# maintenance_panel.net
KiCad netlist of a schematic drawn in EAGLE
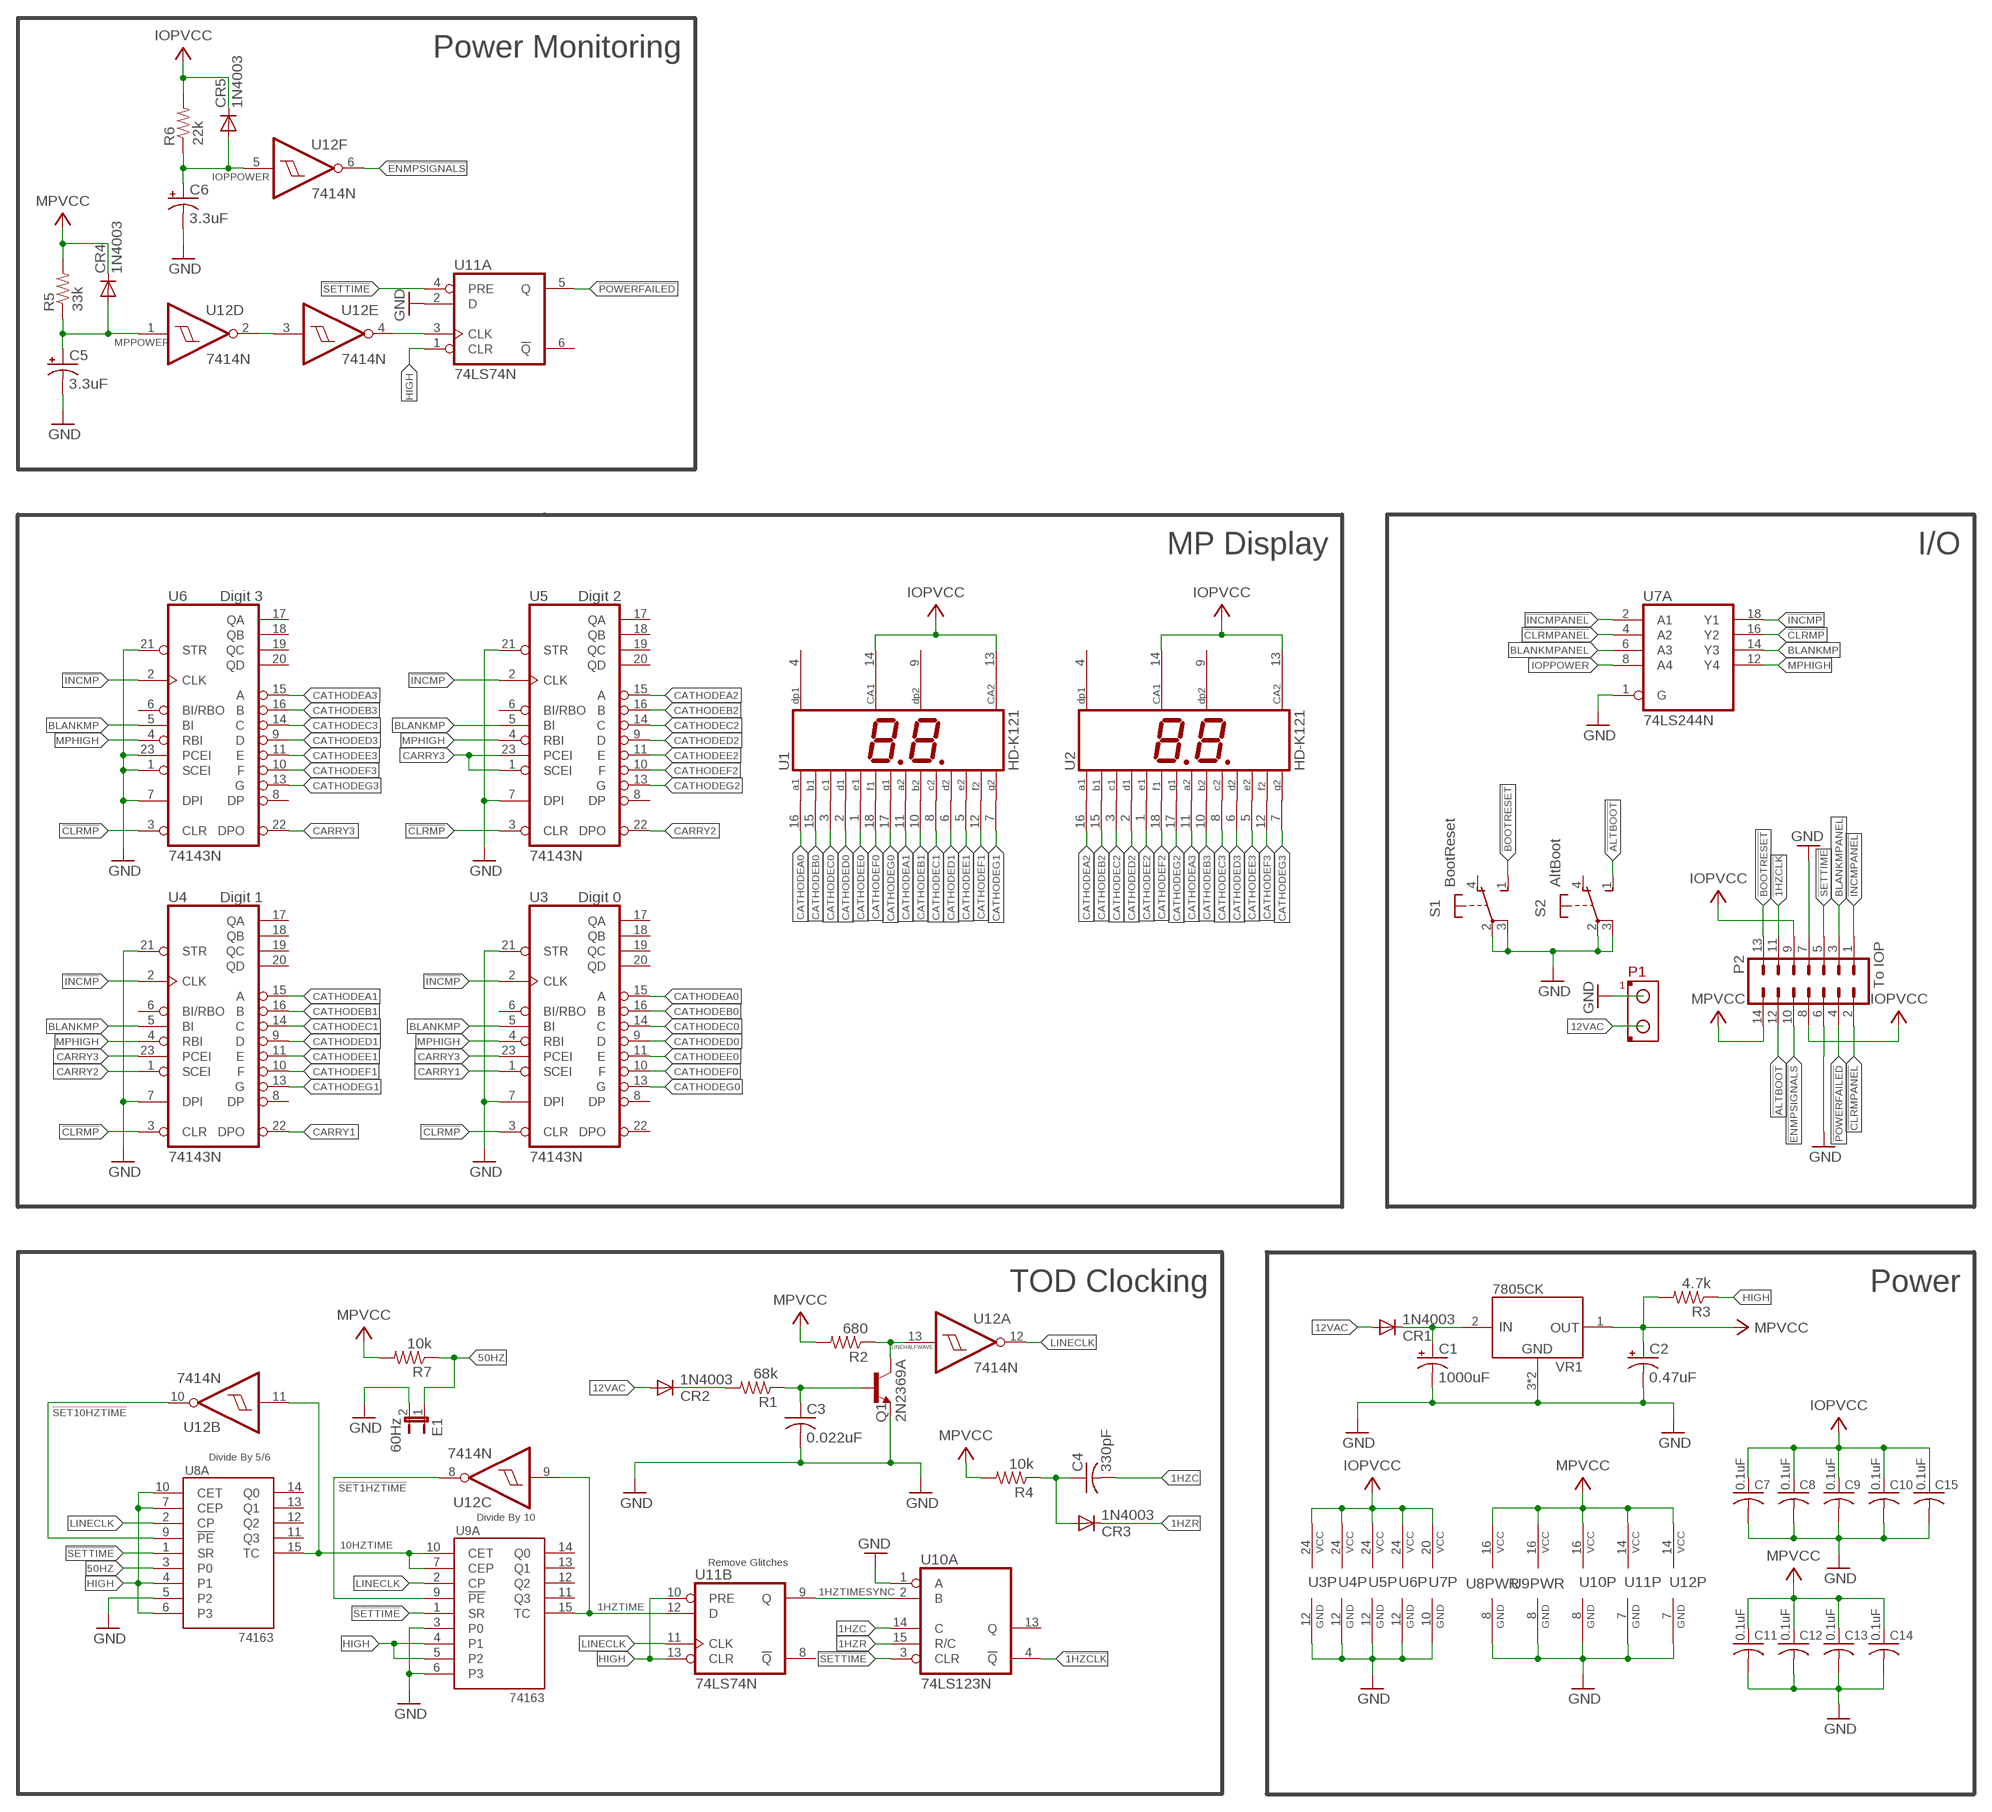
[diagram p0: schematic, sheet 1]

(export (version "E")
  (design (tool "Eeschema 10.0.6"))
  (components
    (comp (ref "C1")
      (value "1000uF")
      (footprint "eagle-import:E25-10")
      (libsource (lib "eagle-import") (part "CPOL-USE25-10AXIAL"))
    )
    (comp (ref "C2")
      (value "0.47uF")
      (footprint "eagle-import:E15-5")
      (libsource (lib "eagle-import") (part "CPOL-USE15-5AXIAL"))
    )
    (comp (ref "C3")
      (value "0.022uF")
      (footprint "eagle-import:C075-052X106")
      (libsource (lib "eagle-import") (part "C-US075-052X106"))
    )
    (comp (ref "C4")
      (value "330pF")
      (footprint "eagle-import:C075-032X103")
      (libsource (lib "eagle-import") (part "C-US075-032X103"))
    )
    (comp (ref "C5")
      (value "3.3uF")
      (footprint "eagle-import:E15-5")
      (libsource (lib "eagle-import") (part "CPOL-USE15-5AXIAL"))
    )
    (comp (ref "C6")
      (value "3.3uF")
      (footprint "eagle-import:E15-5")
      (libsource (lib "eagle-import") (part "CPOL-USE15-5AXIAL"))
    )
    (comp (ref "C7")
      (value "0.1uF")
      (footprint "eagle-import:C075-032X103")
      (libsource (lib "eagle-import") (part "C-US075-032X103"))
    )
    (comp (ref "C8")
      (value "0.1uF")
      (footprint "eagle-import:C075-032X103")
      (libsource (lib "eagle-import") (part "C-US075-032X103"))
    )
    (comp (ref "C9")
      (value "0.1uF")
      (footprint "eagle-import:C075-032X103")
      (libsource (lib "eagle-import") (part "C-US075-032X103"))
    )
    (comp (ref "C10")
      (value "0.1uF")
      (footprint "eagle-import:C075-032X103")
      (libsource (lib "eagle-import") (part "C-US075-032X103"))
    )
    (comp (ref "C11")
      (value "0.1uF")
      (footprint "eagle-import:C075-032X103")
      (libsource (lib "eagle-import") (part "C-US075-032X103"))
    )
    (comp (ref "C12")
      (value "0.1uF")
      (footprint "eagle-import:C075-032X103")
      (libsource (lib "eagle-import") (part "C-US075-032X103"))
    )
    (comp (ref "C13")
      (value "0.1uF")
      (footprint "eagle-import:C075-032X103")
      (libsource (lib "eagle-import") (part "C-US075-032X103"))
    )
    (comp (ref "C14")
      (value "0.1uF")
      (footprint "eagle-import:C075-032X103")
      (libsource (lib "eagle-import") (part "C-US075-032X103"))
    )
    (comp (ref "C15")
      (value "0.1uF")
      (footprint "eagle-import:C075-032X103")
      (libsource (lib "eagle-import") (part "C-US075-032X103"))
    )
    (comp (ref "CR1")
      (value "1N4003")
      (footprint "eagle-import:DO41-10")
      (libsource (lib "eagle-import") (part "1N4004"))
    )
    (comp (ref "CR2")
      (value "1N4003")
      (footprint "eagle-import:DO41-10")
      (libsource (lib "eagle-import") (part "1N4004"))
    )
    (comp (ref "CR3")
      (value "1N4003")
      (footprint "eagle-import:DO41-10")
      (libsource (lib "eagle-import") (part "1N4004"))
    )
    (comp (ref "CR4")
      (value "1N4003")
      (footprint "eagle-import:DO41-10")
      (libsource (lib "eagle-import") (part "1N4004"))
    )
    (comp (ref "CR5")
      (value "1N4003")
      (footprint "eagle-import:DO41-10")
      (libsource (lib "eagle-import") (part "1N4004"))
    )
    (comp (ref "E1")
      (value "60Hz")
      (footprint "eagle-import:JP1")
      (libsource (lib "eagle-import") (part "JP1E"))
    )
    (comp (ref "P1")
      (value "XEROX-RTC-2X1")
      (footprint "eagle-import:XEROX-RTC-2X1")
      (libsource (lib "eagle-import") (part "XEROX-RTC-2X1"))
    )
    (comp (ref "P2")
      (value "To IOP")
      (footprint "eagle-import:MA07-2")
      (libsource (lib "eagle-import") (part "MA07-2"))
    )
    (comp (ref "Q1")
      (value "2N2369A")
      (footprint "eagle-import:TO18")
      (libsource (lib "eagle-import") (part "-NPN-TO18-EBC2N2369A"))
    )
    (comp (ref "R1")
      (value "68k")
      (footprint "eagle-import:0207_10")
      (libsource (lib "eagle-import") (part "R-US_0207/10"))
    )
    (comp (ref "R2")
      (value "680")
      (footprint "eagle-import:0207_10")
      (libsource (lib "eagle-import") (part "R-US_0207/10"))
    )
    (comp (ref "R3")
      (value "4.7k")
      (footprint "eagle-import:0207_10")
      (libsource (lib "eagle-import") (part "R-US_0207/10"))
    )
    (comp (ref "R4")
      (value "10k")
      (footprint "eagle-import:0207_10")
      (libsource (lib "eagle-import") (part "R-US_0207/10"))
    )
    (comp (ref "R5")
      (value "33k")
      (footprint "eagle-import:0207_10")
      (libsource (lib "eagle-import") (part "R-US_0207/10"))
    )
    (comp (ref "R6")
      (value "22k")
      (footprint "eagle-import:0207_10")
      (libsource (lib "eagle-import") (part "R-US_0207/10"))
    )
    (comp (ref "R7")
      (value "10k")
      (footprint "eagle-import:0207_10")
      (libsource (lib "eagle-import") (part "R-US_0207/10"))
    )
    (comp (ref "S1")
      (value "BootReset")
      (footprint "eagle-import:SRK")
      (libsource (lib "eagle-import") (part "SRK"))
    )
    (comp (ref "S2")
      (value "AltBoot")
      (footprint "eagle-import:SRK")
      (libsource (lib "eagle-import") (part "SRK"))
    )
    (comp (ref "U1")
      (value "HD-K121")
      (footprint "eagle-import:HDSP-R")
      (libsource (lib "eagle-import") (part "HD-K121"))
    )
    (comp (ref "U2")
      (value "HD-K121")
      (footprint "eagle-import:HDSP-R")
      (libsource (lib "eagle-import") (part "HD-K121"))
    )
    (comp (ref "U3")
      (value "74143N")
      (footprint "eagle-import:DIL24-6")
      (libsource (lib "eagle-import") (part "74143N"))
    )
    (comp (ref "U4")
      (value "74143N")
      (footprint "eagle-import:DIL24-6")
      (libsource (lib "eagle-import") (part "74143N"))
    )
    (comp (ref "U5")
      (value "74143N")
      (footprint "eagle-import:DIL24-6")
      (libsource (lib "eagle-import") (part "74143N"))
    )
    (comp (ref "U6")
      (value "74143N")
      (footprint "eagle-import:DIL24-6")
      (libsource (lib "eagle-import") (part "74143N"))
    )
    (comp (ref "U7")
      (value "74LS244N")
      (footprint "eagle-import:DIL20")
      (libsource (lib "eagle-import") (part "74244NLS"))
    )
    (comp (ref "U8")
      (value "74163")
      (footprint "eagle-import:DIL16")
      (libsource (lib "eagle-import") (part "74163"))
    )
    (comp (ref "U9")
      (value "74163")
      (footprint "eagle-import:DIL16")
      (libsource (lib "eagle-import") (part "74163"))
    )
    (comp (ref "U10")
      (value "74LS123N")
      (footprint "eagle-import:DIL16")
      (libsource (lib "eagle-import") (part "74123NLS"))
    )
    (comp (ref "U11")
      (value "74LS74N")
      (footprint "eagle-import:DIL14")
      (libsource (lib "eagle-import") (part "7474NLS"))
    )
    (comp (ref "U12")
      (value "7414N")
      (footprint "eagle-import:DIL14")
      (libsource (lib "eagle-import") (part "7414N"))
    )
    (comp (ref "VR1")
      (value "7805CK")
      (footprint "eagle-import:TO3-78")
      (libsource (lib "eagle-import") (part "7805CK"))
    )
  )
  (nets
    (net (code "1") (name "/1HZTIME") (class "Default")
      (node (ref "U11") (pin "12") (pinfunction "D_12") (pintype "input"))
      (node (ref "U12") (pin "9") (pinfunction "I_9") (pintype "input"))
      (node (ref "U9") (pin "15") (pinfunction "TC_15") (pintype "output"))
    )
    (net (code "2") (name "/1HZTIMESYNC") (class "Default")
      (node (ref "U10") (pin "2") (pinfunction "B_2") (pintype "input"))
      (node (ref "U11") (pin "9") (pinfunction "Q_9") (pintype "output"))
    )
    (net (code "3") (name "/10HZTIME") (class "Default")
      (node (ref "U12") (pin "11") (pinfunction "I_11") (pintype "input"))
      (node (ref "U8") (pin "15") (pinfunction "TC_15") (pintype "output"))
      (node (ref "U9") (pin "10") (pinfunction "CET_10") (pintype "input"))
      (node (ref "U9") (pin "7") (pinfunction "CEP_7") (pintype "input"))
    )
    (net (code "4") (name "/LINEHALFWAVE") (class "Default")
      (node (ref "Q1") (pin "3") (pinfunction "C_3") (pintype "passive"))
      (node (ref "R2") (pin "1") (pinfunction "1_1") (pintype "passive"))
      (node (ref "U12") (pin "13") (pinfunction "I_13") (pintype "input"))
    )
    (net (code "5") (name "/MPPOWER") (class "Default")
      (node (ref "C5") (pin "+") (pinfunction "+_+") (pintype "passive"))
      (node (ref "CR4") (pin "A") (pinfunction "A_A") (pintype "passive"))
      (node (ref "R5") (pin "1") (pinfunction "1_1") (pintype "passive"))
      (node (ref "U12") (pin "1") (pinfunction "I_1") (pintype "input"))
    )
    (net (code "6") (name "/~{1HZCLK}") (class "Default")
      (node (ref "P2") (pin "11") (pinfunction "11_11") (pintype "passive"))
      (node (ref "U10") (pin "4") (pinfunction "~{Q}_4") (pintype "output"))
    )
    (net (code "7") (name "/~{ALTBOOT}") (class "Default")
      (node (ref "P2") (pin "12") (pinfunction "12_12") (pintype "passive"))
      (node (ref "S2") (pin "1") (pinfunction "S_1") (pintype "passive"))
    )
    (net (code "8") (name "/~{BOOTRESET}") (class "Default")
      (node (ref "P2") (pin "13") (pinfunction "13_13") (pintype "passive"))
      (node (ref "S1") (pin "1") (pinfunction "S_1") (pintype "passive"))
    )
    (net (code "9") (name "/~{CLRMPANEL}") (class "Default")
      (node (ref "P2") (pin "2") (pinfunction "2_2") (pintype "passive"))
      (node (ref "U7") (pin "4") (pinfunction "A2_4") (pintype "input"))
    )
    (net (code "10") (name "/~{CLRMP}") (class "Default")
      (node (ref "U3") (pin "3") (pinfunction "CLR_3") (pintype "input"))
      (node (ref "U4") (pin "3") (pinfunction "CLR_3") (pintype "input"))
      (node (ref "U5") (pin "3") (pinfunction "CLR_3") (pintype "input"))
      (node (ref "U6") (pin "3") (pinfunction "CLR_3") (pintype "input"))
      (node (ref "U7") (pin "16") (pinfunction "Y2_16") (pintype "tri_state"))
    )
    (net (code "11") (name "/~{ENMPSIGNALS}") (class "Default")
      (node (ref "P2") (pin "10") (pinfunction "10_10") (pintype "passive"))
      (node (ref "U12") (pin "6") (pinfunction "O_6") (pintype "output"))
    )
    (net (code "12") (name "/~{INCMPANEL}") (class "Default")
      (node (ref "P2") (pin "1") (pinfunction "1_1") (pintype "passive"))
      (node (ref "U7") (pin "2") (pinfunction "A1_2") (pintype "input"))
    )
    (net (code "13") (name "/~{INCMP}") (class "Default")
      (node (ref "U3") (pin "2") (pinfunction "CLK_2") (pintype "input"))
      (node (ref "U4") (pin "2") (pinfunction "CLK_2") (pintype "input"))
      (node (ref "U5") (pin "2") (pinfunction "CLK_2") (pintype "input"))
      (node (ref "U6") (pin "2") (pinfunction "CLK_2") (pintype "input"))
      (node (ref "U7") (pin "18") (pinfunction "Y1_18") (pintype "tri_state"))
    )
    (net (code "14") (name "/~{POWERFAILED}") (class "Default")
      (node (ref "P2") (pin "4") (pinfunction "4_4") (pintype "passive"))
      (node (ref "U11") (pin "5") (pinfunction "Q_5") (pintype "output"))
    )
    (net (code "15") (name "/~{SET1HZTIME}") (class "Default")
      (node (ref "U12") (pin "8") (pinfunction "O_8") (pintype "output"))
      (node (ref "U9") (pin "9") (pinfunction "~{PE}_9") (pintype "input"))
    )
    (net (code "16") (name "/~{SET10HZTIME}") (class "Default")
      (node (ref "U12") (pin "10") (pinfunction "O_10") (pintype "output"))
      (node (ref "U8") (pin "9") (pinfunction "~{PE}_9") (pintype "input"))
    )
    (net (code "17") (name "/~{SETTIME}") (class "Default")
      (node (ref "P2") (pin "5") (pinfunction "5_5") (pintype "passive"))
      (node (ref "U10") (pin "3") (pinfunction "CLR_3") (pintype "input"))
      (node (ref "U11") (pin "4") (pinfunction "PRE_4") (pintype "input"))
      (node (ref "U8") (pin "1") (pinfunction "SR_1") (pintype "input"))
      (node (ref "U9") (pin "1") (pinfunction "SR_1") (pintype "input"))
    )
    (net (code "18") (name "1HZC") (class "Default")
      (node (ref "C4") (pin "2") (pinfunction "2_2") (pintype "passive"))
      (node (ref "U10") (pin "14") (pinfunction "C_14") (pintype "input"))
    )
    (net (code "19") (name "1HZR") (class "Default")
      (node (ref "CR3") (pin "C") (pinfunction "C_C") (pintype "passive"))
      (node (ref "U10") (pin "15") (pinfunction "R/C_15") (pintype "input"))
    )
    (net (code "20") (name "12VAC") (class "Default")
      (node (ref "CR1") (pin "A") (pinfunction "A_A") (pintype "passive"))
      (node (ref "CR2") (pin "A") (pinfunction "A_A") (pintype "passive"))
      (node (ref "P1") (pin "2") (pinfunction "2_2") (pintype "passive"))
    )
    (net (code "21") (name "50HZ") (class "Default")
      (node (ref "E1") (pin "1") (pinfunction "1_1") (pintype "passive"))
      (node (ref "R7") (pin "1") (pinfunction "1_1") (pintype "passive"))
      (node (ref "U8") (pin "3") (pinfunction "P0_3") (pintype "input"))
    )
    (net (code "22") (name "BLANKMP") (class "Default")
      (node (ref "U3") (pin "5") (pinfunction "BI_5") (pintype "input"))
      (node (ref "U4") (pin "5") (pinfunction "BI_5") (pintype "input"))
      (node (ref "U5") (pin "5") (pinfunction "BI_5") (pintype "input"))
      (node (ref "U6") (pin "5") (pinfunction "BI_5") (pintype "input"))
      (node (ref "U7") (pin "14") (pinfunction "Y3_14") (pintype "tri_state"))
    )
    (net (code "23") (name "BLANKMPANEL") (class "Default")
      (node (ref "P2") (pin "3") (pinfunction "3_3") (pintype "passive"))
      (node (ref "U7") (pin "6") (pinfunction "A3_6") (pintype "input"))
    )
    (net (code "24") (name "CARRY1") (class "Default")
      (node (ref "U3") (pin "1") (pinfunction "SCEI_1") (pintype "input"))
      (node (ref "U4") (pin "22") (pinfunction "DPO_22") (pintype "output"))
    )
    (net (code "25") (name "CARRY2") (class "Default")
      (node (ref "U4") (pin "1") (pinfunction "SCEI_1") (pintype "input"))
      (node (ref "U5") (pin "22") (pinfunction "DPO_22") (pintype "output"))
    )
    (net (code "26") (name "CARRY3") (class "Default")
      (node (ref "U3") (pin "23") (pinfunction "PCEI_23") (pintype "input"))
      (node (ref "U4") (pin "23") (pinfunction "PCEI_23") (pintype "input"))
      (node (ref "U5") (pin "1") (pinfunction "SCEI_1") (pintype "input"))
      (node (ref "U5") (pin "23") (pinfunction "PCEI_23") (pintype "input"))
      (node (ref "U6") (pin "22") (pinfunction "DPO_22") (pintype "output"))
    )
    (net (code "27") (name "CATHODEA0") (class "Default")
      (node (ref "U1") (pin "16") (pinfunction "A1_16") (pintype "passive"))
      (node (ref "U3") (pin "15") (pinfunction "A_15") (pintype "open_collector"))
    )
    (net (code "28") (name "CATHODEA1") (class "Default")
      (node (ref "U1") (pin "11") (pinfunction "A2_11") (pintype "passive"))
      (node (ref "U4") (pin "15") (pinfunction "A_15") (pintype "open_collector"))
    )
    (net (code "29") (name "CATHODEA2") (class "Default")
      (node (ref "U2") (pin "16") (pinfunction "A1_16") (pintype "passive"))
      (node (ref "U5") (pin "15") (pinfunction "A_15") (pintype "open_collector"))
    )
    (net (code "30") (name "CATHODEA3") (class "Default")
      (node (ref "U2") (pin "11") (pinfunction "A2_11") (pintype "passive"))
      (node (ref "U6") (pin "15") (pinfunction "A_15") (pintype "open_collector"))
    )
    (net (code "31") (name "CATHODEB0") (class "Default")
      (node (ref "U1") (pin "15") (pinfunction "B1_15") (pintype "passive"))
      (node (ref "U3") (pin "16") (pinfunction "B_16") (pintype "open_collector"))
    )
    (net (code "32") (name "CATHODEB1") (class "Default")
      (node (ref "U1") (pin "10") (pinfunction "B2_10") (pintype "passive"))
      (node (ref "U4") (pin "16") (pinfunction "B_16") (pintype "open_collector"))
    )
    (net (code "33") (name "CATHODEB2") (class "Default")
      (node (ref "U2") (pin "15") (pinfunction "B1_15") (pintype "passive"))
      (node (ref "U5") (pin "16") (pinfunction "B_16") (pintype "open_collector"))
    )
    (net (code "34") (name "CATHODEB3") (class "Default")
      (node (ref "U2") (pin "10") (pinfunction "B2_10") (pintype "passive"))
      (node (ref "U6") (pin "16") (pinfunction "B_16") (pintype "open_collector"))
    )
    (net (code "35") (name "CATHODEC0") (class "Default")
      (node (ref "U1") (pin "3") (pinfunction "C1_3") (pintype "passive"))
      (node (ref "U3") (pin "14") (pinfunction "C_14") (pintype "open_collector"))
    )
    (net (code "36") (name "CATHODEC1") (class "Default")
      (node (ref "U1") (pin "8") (pinfunction "C2_8") (pintype "passive"))
      (node (ref "U4") (pin "14") (pinfunction "C_14") (pintype "open_collector"))
    )
    (net (code "37") (name "CATHODEC2") (class "Default")
      (node (ref "U2") (pin "3") (pinfunction "C1_3") (pintype "passive"))
      (node (ref "U5") (pin "14") (pinfunction "C_14") (pintype "open_collector"))
    )
    (net (code "38") (name "CATHODEC3") (class "Default")
      (node (ref "U2") (pin "8") (pinfunction "C2_8") (pintype "passive"))
      (node (ref "U6") (pin "14") (pinfunction "C_14") (pintype "open_collector"))
    )
    (net (code "39") (name "CATHODED0") (class "Default")
      (node (ref "U1") (pin "2") (pinfunction "D1_2") (pintype "passive"))
      (node (ref "U3") (pin "9") (pinfunction "D_9") (pintype "open_collector"))
    )
    (net (code "40") (name "CATHODED1") (class "Default")
      (node (ref "U1") (pin "6") (pinfunction "D2_6") (pintype "passive"))
      (node (ref "U4") (pin "9") (pinfunction "D_9") (pintype "open_collector"))
    )
    (net (code "41") (name "CATHODED2") (class "Default")
      (node (ref "U2") (pin "2") (pinfunction "D1_2") (pintype "passive"))
      (node (ref "U5") (pin "9") (pinfunction "D_9") (pintype "open_collector"))
    )
    (net (code "42") (name "CATHODED3") (class "Default")
      (node (ref "U2") (pin "6") (pinfunction "D2_6") (pintype "passive"))
      (node (ref "U6") (pin "9") (pinfunction "D_9") (pintype "open_collector"))
    )
    (net (code "43") (name "CATHODEE0") (class "Default")
      (node (ref "U1") (pin "1") (pinfunction "E1_1") (pintype "passive"))
      (node (ref "U3") (pin "11") (pinfunction "E_11") (pintype "open_collector"))
    )
    (net (code "44") (name "CATHODEE1") (class "Default")
      (node (ref "U1") (pin "5") (pinfunction "E2_5") (pintype "passive"))
      (node (ref "U4") (pin "11") (pinfunction "E_11") (pintype "open_collector"))
    )
    (net (code "45") (name "CATHODEE2") (class "Default")
      (node (ref "U2") (pin "1") (pinfunction "E1_1") (pintype "passive"))
      (node (ref "U5") (pin "11") (pinfunction "E_11") (pintype "open_collector"))
    )
    (net (code "46") (name "CATHODEE3") (class "Default")
      (node (ref "U2") (pin "5") (pinfunction "E2_5") (pintype "passive"))
      (node (ref "U6") (pin "11") (pinfunction "E_11") (pintype "open_collector"))
    )
    (net (code "47") (name "CATHODEF0") (class "Default")
      (node (ref "U1") (pin "18") (pinfunction "F1_18") (pintype "passive"))
      (node (ref "U3") (pin "10") (pinfunction "F_10") (pintype "open_collector"))
    )
    (net (code "48") (name "CATHODEF1") (class "Default")
      (node (ref "U1") (pin "12") (pinfunction "F2_12") (pintype "passive"))
      (node (ref "U4") (pin "10") (pinfunction "F_10") (pintype "open_collector"))
    )
    (net (code "49") (name "CATHODEF2") (class "Default")
      (node (ref "U2") (pin "18") (pinfunction "F1_18") (pintype "passive"))
      (node (ref "U5") (pin "10") (pinfunction "F_10") (pintype "open_collector"))
    )
    (net (code "50") (name "CATHODEF3") (class "Default")
      (node (ref "U2") (pin "12") (pinfunction "F2_12") (pintype "passive"))
      (node (ref "U6") (pin "10") (pinfunction "F_10") (pintype "open_collector"))
    )
    (net (code "51") (name "CATHODEG0") (class "Default")
      (node (ref "U1") (pin "17") (pinfunction "G1_17") (pintype "passive"))
      (node (ref "U3") (pin "13") (pinfunction "G_13") (pintype "open_collector"))
    )
    (net (code "52") (name "CATHODEG1") (class "Default")
      (node (ref "U1") (pin "7") (pinfunction "G2_7") (pintype "passive"))
      (node (ref "U4") (pin "13") (pinfunction "G_13") (pintype "open_collector"))
    )
    (net (code "53") (name "CATHODEG2") (class "Default")
      (node (ref "U2") (pin "17") (pinfunction "G1_17") (pintype "passive"))
      (node (ref "U5") (pin "13") (pinfunction "G_13") (pintype "open_collector"))
    )
    (net (code "54") (name "CATHODEG3") (class "Default")
      (node (ref "U2") (pin "7") (pinfunction "G2_7") (pintype "passive"))
      (node (ref "U6") (pin "13") (pinfunction "G_13") (pintype "open_collector"))
    )
    (net (code "55") (name "GND") (class "Default")
      (node (ref "C1") (pin "-") (pinfunction "-_-") (pintype "passive"))
      (node (ref "C10") (pin "2") (pinfunction "2_2") (pintype "passive"))
      (node (ref "C11") (pin "2") (pinfunction "2_2") (pintype "passive"))
      (node (ref "C12") (pin "2") (pinfunction "2_2") (pintype "passive"))
      (node (ref "C13") (pin "2") (pinfunction "2_2") (pintype "passive"))
      (node (ref "C14") (pin "2") (pinfunction "2_2") (pintype "passive"))
      (node (ref "C15") (pin "2") (pinfunction "2_2") (pintype "passive"))
      (node (ref "C2") (pin "-") (pinfunction "-_-") (pintype "passive"))
      (node (ref "C3") (pin "2") (pinfunction "2_2") (pintype "passive"))
      (node (ref "C5") (pin "-") (pinfunction "-_-") (pintype "passive"))
      (node (ref "C6") (pin "-") (pinfunction "-_-") (pintype "passive"))
      (node (ref "C7") (pin "2") (pinfunction "2_2") (pintype "passive"))
      (node (ref "C8") (pin "2") (pinfunction "2_2") (pintype "passive"))
      (node (ref "C9") (pin "2") (pinfunction "2_2") (pintype "passive"))
      (node (ref "E1") (pin "2") (pinfunction "2_2") (pintype "passive"))
      (node (ref "P1") (pin "1") (pinfunction "1_1") (pintype "passive"))
      (node (ref "P2") (pin "6") (pinfunction "6_6") (pintype "passive"))
      (node (ref "P2") (pin "7") (pinfunction "7_7") (pintype "passive"))
      (node (ref "Q1") (pin "1") (pinfunction "E_1") (pintype "passive"))
      (node (ref "S1") (pin "2") (pinfunction "P_2") (pintype "passive"))
      (node (ref "S1") (pin "3") (pinfunction "P_3") (pintype "passive"))
      (node (ref "S2") (pin "2") (pinfunction "P_2") (pintype "passive"))
      (node (ref "S2") (pin "3") (pinfunction "P_3") (pintype "passive"))
      (node (ref "U10") (pin "1") (pinfunction "A_1") (pintype "input"))
      (node (ref "U10") (pin "8") (pinfunction "GND_8") (pintype "power_in"))
      (node (ref "U11") (pin "2") (pinfunction "D_2") (pintype "input"))
      (node (ref "U11") (pin "7") (pinfunction "GND_7") (pintype "power_in"))
      (node (ref "U12") (pin "7") (pinfunction "GND_7") (pintype "power_in"))
      (node (ref "U3") (pin "12") (pinfunction "GND_12") (pintype "power_in"))
      (node (ref "U3") (pin "21") (pinfunction "STR_21") (pintype "input"))
      (node (ref "U3") (pin "7") (pinfunction "DPI_7") (pintype "input"))
      (node (ref "U4") (pin "12") (pinfunction "GND_12") (pintype "power_in"))
      (node (ref "U4") (pin "21") (pinfunction "STR_21") (pintype "input"))
      (node (ref "U4") (pin "7") (pinfunction "DPI_7") (pintype "input"))
      (node (ref "U5") (pin "12") (pinfunction "GND_12") (pintype "power_in"))
      (node (ref "U5") (pin "21") (pinfunction "STR_21") (pintype "input"))
      (node (ref "U5") (pin "7") (pinfunction "DPI_7") (pintype "input"))
      (node (ref "U6") (pin "1") (pinfunction "SCEI_1") (pintype "input"))
      (node (ref "U6") (pin "12") (pinfunction "GND_12") (pintype "power_in"))
      (node (ref "U6") (pin "21") (pinfunction "STR_21") (pintype "input"))
      (node (ref "U6") (pin "23") (pinfunction "PCEI_23") (pintype "input"))
      (node (ref "U6") (pin "7") (pinfunction "DPI_7") (pintype "input"))
      (node (ref "U7") (pin "1") (pinfunction "G_1") (pintype "input"))
      (node (ref "U7") (pin "10") (pinfunction "GND_10") (pintype "power_in"))
      (node (ref "U8") (pin "5") (pinfunction "P2_5") (pintype "input"))
      (node (ref "U8") (pin "8") (pinfunction "GND_8") (pintype "power_in"))
      (node (ref "U9") (pin "3") (pinfunction "P0_3") (pintype "input"))
      (node (ref "U9") (pin "6") (pinfunction "P3_6") (pintype "input"))
      (node (ref "U9") (pin "8") (pinfunction "GND_8") (pintype "power_in"))
      (node (ref "VR1") (pin "3") (pinfunction "GND_3") (pintype "bidirectional"))
      (node (ref "VR1") (pin "3@") (pinfunction "GND_3@") (pintype "bidirectional"))
    )
    (net (code "56") (name "HIGH") (class "Default")
      (node (ref "R3") (pin "1") (pinfunction "1_1") (pintype "passive"))
      (node (ref "U11") (pin "1") (pinfunction "CLR_1") (pintype "input"))
      (node (ref "U11") (pin "10") (pinfunction "PRE_10") (pintype "input"))
      (node (ref "U11") (pin "13") (pinfunction "CLR_13") (pintype "input"))
      (node (ref "U8") (pin "10") (pinfunction "CET_10") (pintype "input"))
      (node (ref "U8") (pin "4") (pinfunction "P1_4") (pintype "input"))
      (node (ref "U8") (pin "6") (pinfunction "P3_6") (pintype "input"))
      (node (ref "U8") (pin "7") (pinfunction "CEP_7") (pintype "input"))
      (node (ref "U9") (pin "4") (pinfunction "P1_4") (pintype "input"))
      (node (ref "U9") (pin "5") (pinfunction "P2_5") (pintype "input"))
    )
    (net (code "57") (name "IOPPOWER") (class "Default")
      (node (ref "C6") (pin "+") (pinfunction "+_+") (pintype "passive"))
      (node (ref "CR5") (pin "A") (pinfunction "A_A") (pintype "passive"))
      (node (ref "R6") (pin "1") (pinfunction "1_1") (pintype "passive"))
      (node (ref "U12") (pin "5") (pinfunction "I_5") (pintype "input"))
      (node (ref "U7") (pin "8") (pinfunction "A4_8") (pintype "input"))
    )
    (net (code "58") (name "IOPVCC") (class "Default")
      (node (ref "C10") (pin "1") (pinfunction "1_1") (pintype "passive"))
      (node (ref "C15") (pin "1") (pinfunction "1_1") (pintype "passive"))
      (node (ref "C7") (pin "1") (pinfunction "1_1") (pintype "passive"))
      (node (ref "C8") (pin "1") (pinfunction "1_1") (pintype "passive"))
      (node (ref "C9") (pin "1") (pinfunction "1_1") (pintype "passive"))
      (node (ref "CR5") (pin "C") (pinfunction "C_C") (pintype "passive"))
      (node (ref "P2") (pin "8") (pinfunction "8_8") (pintype "passive"))
      (node (ref "P2") (pin "9") (pinfunction "9_9") (pintype "passive"))
      (node (ref "R6") (pin "2") (pinfunction "2_2") (pintype "passive"))
      (node (ref "U1") (pin "13") (pinfunction "CA2_13") (pintype "passive"))
      (node (ref "U1") (pin "14") (pinfunction "CA1_14") (pintype "passive"))
      (node (ref "U2") (pin "13") (pinfunction "CA2_13") (pintype "passive"))
      (node (ref "U2") (pin "14") (pinfunction "CA1_14") (pintype "passive"))
      (node (ref "U3") (pin "24") (pinfunction "VCC_24") (pintype "power_in"))
      (node (ref "U4") (pin "24") (pinfunction "VCC_24") (pintype "power_in"))
      (node (ref "U5") (pin "24") (pinfunction "VCC_24") (pintype "power_in"))
      (node (ref "U6") (pin "24") (pinfunction "VCC_24") (pintype "power_in"))
      (node (ref "U7") (pin "20") (pinfunction "VCC_20") (pintype "power_in"))
    )
    (net (code "59") (name "LINECLK") (class "Default")
      (node (ref "U11") (pin "11") (pinfunction "CLK_11") (pintype "input"))
      (node (ref "U12") (pin "12") (pinfunction "O_12") (pintype "output"))
      (node (ref "U8") (pin "2") (pinfunction "CP_2") (pintype "input"))
      (node (ref "U9") (pin "2") (pinfunction "CP_2") (pintype "input"))
    )
    (net (code "60") (name "MPHIGH") (class "Default")
      (node (ref "U3") (pin "4") (pinfunction "RBI_4") (pintype "input"))
      (node (ref "U4") (pin "4") (pinfunction "RBI_4") (pintype "input"))
      (node (ref "U5") (pin "4") (pinfunction "RBI_4") (pintype "input"))
      (node (ref "U6") (pin "4") (pinfunction "RBI_4") (pintype "input"))
      (node (ref "U7") (pin "12") (pinfunction "Y4_12") (pintype "tri_state"))
    )
    (net (code "61") (name "MPVCC") (class "Default")
      (node (ref "C11") (pin "1") (pinfunction "1_1") (pintype "passive"))
      (node (ref "C12") (pin "1") (pinfunction "1_1") (pintype "passive"))
      (node (ref "C13") (pin "1") (pinfunction "1_1") (pintype "passive"))
      (node (ref "C14") (pin "1") (pinfunction "1_1") (pintype "passive"))
      (node (ref "C2") (pin "+") (pinfunction "+_+") (pintype "passive"))
      (node (ref "CR4") (pin "C") (pinfunction "C_C") (pintype "passive"))
      (node (ref "P2") (pin "14") (pinfunction "14_14") (pintype "passive"))
      (node (ref "R2") (pin "2") (pinfunction "2_2") (pintype "passive"))
      (node (ref "R3") (pin "2") (pinfunction "2_2") (pintype "passive"))
      (node (ref "R4") (pin "2") (pinfunction "2_2") (pintype "passive"))
      (node (ref "R5") (pin "2") (pinfunction "2_2") (pintype "passive"))
      (node (ref "R7") (pin "2") (pinfunction "2_2") (pintype "passive"))
      (node (ref "U10") (pin "16") (pinfunction "VCC_16") (pintype "power_in"))
      (node (ref "U11") (pin "14") (pinfunction "VCC_14") (pintype "power_in"))
      (node (ref "U12") (pin "14") (pinfunction "VCC_14") (pintype "power_in"))
      (node (ref "U8") (pin "16") (pinfunction "VCC_16") (pintype "power_in"))
      (node (ref "U9") (pin "16") (pinfunction "VCC_16") (pintype "power_in"))
      (node (ref "VR1") (pin "1") (pinfunction "OUT_1") (pintype "bidirectional"))
    )
    (net (code "62") (name "Net-(C4-Pad1)") (class "Default")
      (node (ref "C4") (pin "1") (pinfunction "1_1") (pintype "passive"))
      (node (ref "CR3") (pin "A") (pinfunction "A_A") (pintype "passive"))
      (node (ref "R4") (pin "1") (pinfunction "1_1") (pintype "passive"))
    )
    (net (code "63") (name "Net-(CR2-PadC)") (class "Default")
      (node (ref "CR2") (pin "C") (pinfunction "C_C") (pintype "passive"))
      (node (ref "R1") (pin "2") (pinfunction "2_2") (pintype "passive"))
    )
    (net (code "64") (name "Net-(Q1-B)") (class "Default")
      (node (ref "C3") (pin "1") (pinfunction "1_1") (pintype "passive"))
      (node (ref "Q1") (pin "2") (pinfunction "B_2") (pintype "passive"))
      (node (ref "R1") (pin "1") (pinfunction "1_1") (pintype "passive"))
    )
    (net (code "65") (name "Net-(U11A-CLK)") (class "Default")
      (node (ref "U11") (pin "3") (pinfunction "CLK_3") (pintype "input"))
      (node (ref "U12") (pin "4") (pinfunction "O_4") (pintype "output"))
    )
    (net (code "66") (name "Net-(U12D-O)") (class "Default")
      (node (ref "U12") (pin "2") (pinfunction "O_2") (pintype "output"))
      (node (ref "U12") (pin "3") (pinfunction "I_3") (pintype "input"))
    )
    (net (code "67") (name "Net-(VR1-IN)") (class "Default")
      (node (ref "C1") (pin "+") (pinfunction "+_+") (pintype "passive"))
      (node (ref "CR1") (pin "C") (pinfunction "C_C") (pintype "passive"))
      (node (ref "VR1") (pin "2") (pinfunction "IN_2") (pintype "bidirectional"))
    )
    (net (code "68") (name "unconnected-(S1-O-Pad4)") (class "Default")
      (node (ref "S1") (pin "4") (pinfunction "O_4") (pintype "passive"))
    )
    (net (code "69") (name "unconnected-(S2-O-Pad4)") (class "Default")
      (node (ref "S2") (pin "4") (pinfunction "O_4") (pintype "passive"))
    )
    (net (code "70") (name "unconnected-(U1-DP1-Pad4)") (class "Default")
      (node (ref "U1") (pin "4") (pinfunction "DP1_4") (pintype "passive"))
    )
    (net (code "71") (name "unconnected-(U1-DP2-Pad9)") (class "Default")
      (node (ref "U1") (pin "9") (pinfunction "DP2_9") (pintype "passive"))
    )
    (net (code "72") (name "unconnected-(U2-DP1-Pad4)") (class "Default")
      (node (ref "U2") (pin "4") (pinfunction "DP1_4") (pintype "passive"))
    )
    (net (code "73") (name "unconnected-(U2-DP2-Pad9)") (class "Default")
      (node (ref "U2") (pin "9") (pinfunction "DP2_9") (pintype "passive"))
    )
    (net (code "74") (name "unconnected-(U3A-BI{slash}RBO-Pad6)") (class "Default")
      (node (ref "U3") (pin "6") (pinfunction "BI/RBO_6") (pintype "bidirectional"))
    )
    (net (code "75") (name "unconnected-(U3A-DP-Pad8)") (class "Default")
      (node (ref "U3") (pin "8") (pinfunction "DP_8") (pintype "open_collector"))
    )
    (net (code "76") (name "unconnected-(U3A-DPO-Pad22)") (class "Default")
      (node (ref "U3") (pin "22") (pinfunction "DPO_22") (pintype "output"))
    )
    (net (code "77") (name "unconnected-(U3A-QA-Pad17)") (class "Default")
      (node (ref "U3") (pin "17") (pinfunction "QA_17") (pintype "output"))
    )
    (net (code "78") (name "unconnected-(U3A-QB-Pad18)") (class "Default")
      (node (ref "U3") (pin "18") (pinfunction "QB_18") (pintype "output"))
    )
    (net (code "79") (name "unconnected-(U3A-QC-Pad19)") (class "Default")
      (node (ref "U3") (pin "19") (pinfunction "QC_19") (pintype "output"))
    )
    (net (code "80") (name "unconnected-(U3A-QD-Pad20)") (class "Default")
      (node (ref "U3") (pin "20") (pinfunction "QD_20") (pintype "output"))
    )
    (net (code "81") (name "unconnected-(U4A-BI{slash}RBO-Pad6)") (class "Default")
      (node (ref "U4") (pin "6") (pinfunction "BI/RBO_6") (pintype "bidirectional"))
    )
    (net (code "82") (name "unconnected-(U4A-DP-Pad8)") (class "Default")
      (node (ref "U4") (pin "8") (pinfunction "DP_8") (pintype "open_collector"))
    )
    (net (code "83") (name "unconnected-(U4A-QA-Pad17)") (class "Default")
      (node (ref "U4") (pin "17") (pinfunction "QA_17") (pintype "output"))
    )
    (net (code "84") (name "unconnected-(U4A-QB-Pad18)") (class "Default")
      (node (ref "U4") (pin "18") (pinfunction "QB_18") (pintype "output"))
    )
    (net (code "85") (name "unconnected-(U4A-QC-Pad19)") (class "Default")
      (node (ref "U4") (pin "19") (pinfunction "QC_19") (pintype "output"))
    )
    (net (code "86") (name "unconnected-(U4A-QD-Pad20)") (class "Default")
      (node (ref "U4") (pin "20") (pinfunction "QD_20") (pintype "output"))
    )
    (net (code "87") (name "unconnected-(U5A-BI{slash}RBO-Pad6)") (class "Default")
      (node (ref "U5") (pin "6") (pinfunction "BI/RBO_6") (pintype "bidirectional"))
    )
    (net (code "88") (name "unconnected-(U5A-DP-Pad8)") (class "Default")
      (node (ref "U5") (pin "8") (pinfunction "DP_8") (pintype "open_collector"))
    )
    (net (code "89") (name "unconnected-(U5A-QA-Pad17)") (class "Default")
      (node (ref "U5") (pin "17") (pinfunction "QA_17") (pintype "output"))
    )
    (net (code "90") (name "unconnected-(U5A-QB-Pad18)") (class "Default")
      (node (ref "U5") (pin "18") (pinfunction "QB_18") (pintype "output"))
    )
    (net (code "91") (name "unconnected-(U5A-QC-Pad19)") (class "Default")
      (node (ref "U5") (pin "19") (pinfunction "QC_19") (pintype "output"))
    )
    (net (code "92") (name "unconnected-(U5A-QD-Pad20)") (class "Default")
      (node (ref "U5") (pin "20") (pinfunction "QD_20") (pintype "output"))
    )
    (net (code "93") (name "unconnected-(U6A-BI{slash}RBO-Pad6)") (class "Default")
      (node (ref "U6") (pin "6") (pinfunction "BI/RBO_6") (pintype "bidirectional"))
    )
    (net (code "94") (name "unconnected-(U6A-DP-Pad8)") (class "Default")
      (node (ref "U6") (pin "8") (pinfunction "DP_8") (pintype "open_collector"))
    )
    (net (code "95") (name "unconnected-(U6A-QA-Pad17)") (class "Default")
      (node (ref "U6") (pin "17") (pinfunction "QA_17") (pintype "output"))
    )
    (net (code "96") (name "unconnected-(U6A-QB-Pad18)") (class "Default")
      (node (ref "U6") (pin "18") (pinfunction "QB_18") (pintype "output"))
    )
    (net (code "97") (name "unconnected-(U6A-QC-Pad19)") (class "Default")
      (node (ref "U6") (pin "19") (pinfunction "QC_19") (pintype "output"))
    )
    (net (code "98") (name "unconnected-(U6A-QD-Pad20)") (class "Default")
      (node (ref "U6") (pin "20") (pinfunction "QD_20") (pintype "output"))
    )
    (net (code "99") (name "unconnected-(U8A-Q0-Pad14)") (class "Default")
      (node (ref "U8") (pin "14") (pinfunction "Q0_14") (pintype "output"))
    )
    (net (code "100") (name "unconnected-(U8A-Q1-Pad13)") (class "Default")
      (node (ref "U8") (pin "13") (pinfunction "Q1_13") (pintype "output"))
    )
    (net (code "101") (name "unconnected-(U8A-Q2-Pad12)") (class "Default")
      (node (ref "U8") (pin "12") (pinfunction "Q2_12") (pintype "output"))
    )
    (net (code "102") (name "unconnected-(U8A-Q3-Pad11)") (class "Default")
      (node (ref "U8") (pin "11") (pinfunction "Q3_11") (pintype "output"))
    )
    (net (code "103") (name "unconnected-(U9A-Q0-Pad14)") (class "Default")
      (node (ref "U9") (pin "14") (pinfunction "Q0_14") (pintype "output"))
    )
    (net (code "104") (name "unconnected-(U9A-Q1-Pad13)") (class "Default")
      (node (ref "U9") (pin "13") (pinfunction "Q1_13") (pintype "output"))
    )
    (net (code "105") (name "unconnected-(U9A-Q2-Pad12)") (class "Default")
      (node (ref "U9") (pin "12") (pinfunction "Q2_12") (pintype "output"))
    )
    (net (code "106") (name "unconnected-(U9A-Q3-Pad11)") (class "Default")
      (node (ref "U9") (pin "11") (pinfunction "Q3_11") (pintype "output"))
    )
    (net (code "107") (name "unconnected-(U10A-Q-Pad13)") (class "Default")
      (node (ref "U10") (pin "13") (pinfunction "Q_13") (pintype "output"))
    )
    (net (code "108") (name "unconnected-(U11A-~{Q}-Pad6)") (class "Default")
      (node (ref "U11") (pin "6") (pinfunction "~{Q}_6") (pintype "output"))
    )
    (net (code "109") (name "unconnected-(U11B-~{Q}-Pad8)") (class "Default")
      (node (ref "U11") (pin "8") (pinfunction "~{Q}_8") (pintype "output"))
    )
  )
)
